# MySXMotion-V1_2-001.net
KiCad netlist of a schematic drawn in EAGLE
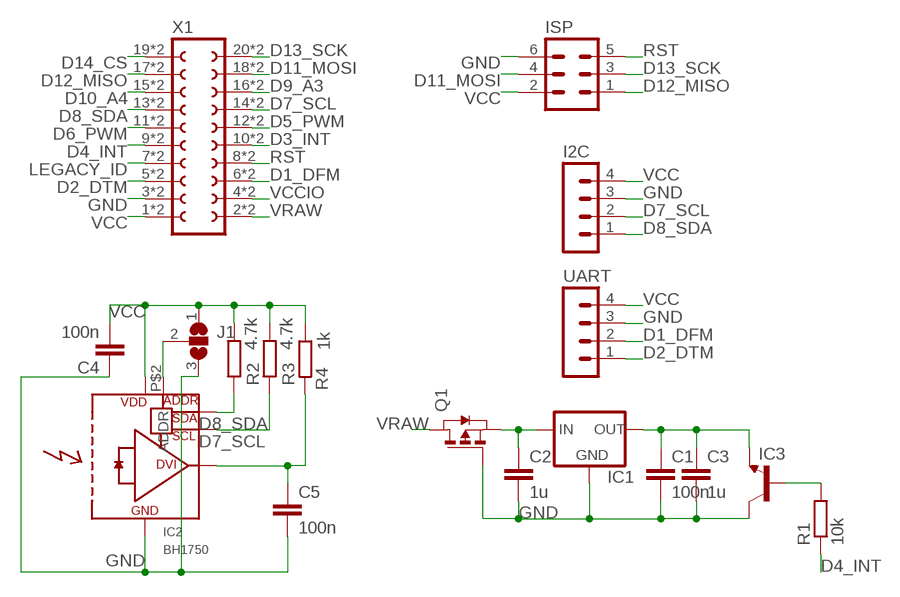
[diagram p0: schematic, sheet 1]

(export (version "E")
  (design (tool "Eeschema 10.0.6"))
  (components
    (comp (ref "C1")
      (value "100n")
      (footprint "eagle-import:C0603")
      (libsource (lib "eagle-import") (part "C-EUC0603"))
    )
    (comp (ref "C2")
      (value "1u")
      (footprint "eagle-import:C0603")
      (libsource (lib "eagle-import") (part "C-EUC0603"))
    )
    (comp (ref "C3")
      (value "1u")
      (footprint "eagle-import:C0805")
      (libsource (lib "eagle-import") (part "C-EUC0805"))
    )
    (comp (ref "C4")
      (value "100n")
      (footprint "eagle-import:C0603")
      (libsource (lib "eagle-import") (part "C-EUC0603"))
    )
    (comp (ref "C5")
      (value "100n")
      (footprint "eagle-import:C0603")
      (libsource (lib "eagle-import") (part "C-EUC0603"))
    )
    (comp (ref "I2C")
      (value "MA04-1")
      (footprint "eagle-import:MA04-1")
      (libsource (lib "eagle-import") (part "MA04-1"))
    )
    (comp (ref "IC1")
      (value "XC63FPM")
      (footprint "eagle-import:SOT23")
      (libsource (lib "eagle-import") (part "XC63FPM"))
    )
    (comp (ref "IC2")
      (value "BH1750")
      (footprint "eagle-import:WSOF6")
      (libsource (lib "eagle-import") (part "BH1750"))
    )
    (comp (ref "IC3")
      (value "-NPN-TO5")
      (footprint "eagle-import:TO5")
      (libsource (lib "eagle-import") (part "-NPN-TO5"))
    )
    (comp (ref "ISP")
      (value "MA03-2")
      (footprint "eagle-import:MA03-2")
      (libsource (lib "eagle-import") (part "MA03-2"))
    )
    (comp (ref "J1")
      (value "SJ2W")
      (footprint "eagle-import:SJ_2")
      (libsource (lib "eagle-import") (part "SJ2W"))
    )
    (comp (ref "Q1")
      (value "PMOSSOT23")
      (footprint "eagle-import:SOT-23")
      (libsource (lib "eagle-import") (part "PMOSSOT23"))
    )
    (comp (ref "R1")
      (value "10k")
      (footprint "eagle-import:R0603")
      (libsource (lib "eagle-import") (part "R-EU_R0603"))
    )
    (comp (ref "R2")
      (value "4.7k")
      (footprint "eagle-import:R0603")
      (libsource (lib "eagle-import") (part "R-EU_R0603"))
    )
    (comp (ref "R3")
      (value "4.7k")
      (footprint "eagle-import:R0603")
      (libsource (lib "eagle-import") (part "R-EU_R0603"))
    )
    (comp (ref "R4")
      (value "1k")
      (footprint "eagle-import:R0603")
      (libsource (lib "eagle-import") (part "R-EU_R0603"))
    )
    (comp (ref "UART")
      (value "MA04-1")
      (footprint "eagle-import:MA04-1")
      (libsource (lib "eagle-import") (part "MA04-1"))
    )
    (comp (ref "X1")
      (value "FE10-2")
      (footprint "eagle-import:FE10-2")
      (libsource (lib "eagle-import") (part "FE10-2"))
    )
  )
  (nets
    (net (code "1") (name "/D1_DFM") (class "Default")
      (node (ref "UART") (pin "2") (pinfunction "2_2") (pintype "passive"))
      (node (ref "X1") (pin "6") (pinfunction "6_6") (pintype "passive"))
      (node (ref "X1") (pin "P$6") (pinfunction "6_P$6") (pintype "passive"))
    )
    (net (code "2") (name "/D2_DTM") (class "Default")
      (node (ref "UART") (pin "1") (pinfunction "1_1") (pintype "passive"))
      (node (ref "X1") (pin "5") (pinfunction "5_5") (pintype "passive"))
      (node (ref "X1") (pin "P$5") (pinfunction "5_P$5") (pintype "passive"))
    )
    (net (code "3") (name "/D3_INT") (class "Default")
      (node (ref "X1") (pin "10") (pinfunction "10_10") (pintype "passive"))
      (node (ref "X1") (pin "P$10") (pinfunction "10_P$10") (pintype "passive"))
    )
    (net (code "4") (name "/D4_INT") (class "Default")
      (node (ref "R1") (pin "1") (pinfunction "1_1") (pintype "passive"))
      (node (ref "X1") (pin "9") (pinfunction "9_9") (pintype "passive"))
      (node (ref "X1") (pin "P$9") (pinfunction "9_P$9") (pintype "passive"))
    )
    (net (code "5") (name "/D5_PWM") (class "Default")
      (node (ref "X1") (pin "12") (pinfunction "12_12") (pintype "passive"))
      (node (ref "X1") (pin "P$12") (pinfunction "12_P$12") (pintype "passive"))
    )
    (net (code "6") (name "/D6_PWM") (class "Default")
      (node (ref "X1") (pin "11") (pinfunction "11_11") (pintype "passive"))
      (node (ref "X1") (pin "P$11") (pinfunction "11_P$11") (pintype "passive"))
    )
    (net (code "7") (name "/D7_SCL") (class "Default")
      (node (ref "I2C") (pin "2") (pinfunction "2_2") (pintype "passive"))
      (node (ref "IC2") (pin "P$6") (pinfunction "SCL_P$6") (pintype "input"))
      (node (ref "R3") (pin "1") (pinfunction "1_1") (pintype "passive"))
      (node (ref "X1") (pin "14") (pinfunction "14_14") (pintype "passive"))
      (node (ref "X1") (pin "P$14") (pinfunction "14_P$14") (pintype "passive"))
    )
    (net (code "8") (name "/D8_SDA") (class "Default")
      (node (ref "I2C") (pin "1") (pinfunction "1_1") (pintype "passive"))
      (node (ref "IC2") (pin "P$4") (pinfunction "SDA_P$4") (pintype "bidirectional"))
      (node (ref "R2") (pin "1") (pinfunction "1_1") (pintype "passive"))
      (node (ref "X1") (pin "13") (pinfunction "13_13") (pintype "passive"))
      (node (ref "X1") (pin "P$13") (pinfunction "13_P$13") (pintype "passive"))
    )
    (net (code "9") (name "/D9_A3") (class "Default")
      (node (ref "X1") (pin "16") (pinfunction "16_16") (pintype "passive"))
      (node (ref "X1") (pin "P$16") (pinfunction "16_P$16") (pintype "passive"))
    )
    (net (code "10") (name "/D10_A4") (class "Default")
      (node (ref "X1") (pin "15") (pinfunction "15_15") (pintype "passive"))
      (node (ref "X1") (pin "P$15") (pinfunction "15_P$15") (pintype "passive"))
    )
    (net (code "11") (name "/D11_MOSI") (class "Default")
      (node (ref "ISP") (pin "4") (pinfunction "4_4") (pintype "passive"))
      (node (ref "X1") (pin "18") (pinfunction "18_18") (pintype "passive"))
      (node (ref "X1") (pin "P$18") (pinfunction "18_P$18") (pintype "passive"))
    )
    (net (code "12") (name "/D12_MISO") (class "Default")
      (node (ref "ISP") (pin "1") (pinfunction "1_1") (pintype "passive"))
      (node (ref "X1") (pin "17") (pinfunction "17_17") (pintype "passive"))
      (node (ref "X1") (pin "P$17") (pinfunction "17_P$17") (pintype "passive"))
    )
    (net (code "13") (name "/D13_SCK") (class "Default")
      (node (ref "ISP") (pin "3") (pinfunction "3_3") (pintype "passive"))
      (node (ref "X1") (pin "20") (pinfunction "20_20") (pintype "passive"))
      (node (ref "X1") (pin "P$20") (pinfunction "20_P$20") (pintype "passive"))
    )
    (net (code "14") (name "/D14_CS") (class "Default")
      (node (ref "X1") (pin "19") (pinfunction "19_19") (pintype "passive"))
      (node (ref "X1") (pin "P$19") (pinfunction "19_P$19") (pintype "passive"))
    )
    (net (code "15") (name "/GND") (class "Default")
      (node (ref "C1") (pin "2") (pinfunction "2_2") (pintype "passive"))
      (node (ref "C2") (pin "2") (pinfunction "2_2") (pintype "passive"))
      (node (ref "C3") (pin "2") (pinfunction "2_2") (pintype "passive"))
      (node (ref "C4") (pin "1") (pinfunction "1_1") (pintype "passive"))
      (node (ref "C5") (pin "2") (pinfunction "2_2") (pintype "passive"))
      (node (ref "I2C") (pin "3") (pinfunction "3_3") (pintype "passive"))
      (node (ref "IC1") (pin "1") (pinfunction "GND_1") (pintype "input"))
      (node (ref "IC2") (pin "P$3") (pinfunction "GND_P$3") (pintype "power_in"))
      (node (ref "IC3") (pin "3") (pinfunction "C_3") (pintype "passive"))
      (node (ref "ISP") (pin "6") (pinfunction "6_6") (pintype "passive"))
      (node (ref "J1") (pin "3") (pinfunction "3_3") (pintype "passive"))
      (node (ref "Q1") (pin "3") (pinfunction "G_3") (pintype "passive"))
      (node (ref "UART") (pin "3") (pinfunction "3_3") (pintype "passive"))
      (node (ref "X1") (pin "3") (pinfunction "3_3") (pintype "passive"))
      (node (ref "X1") (pin "P$3") (pinfunction "3_P$3") (pintype "passive"))
    )
    (net (code "16") (name "/LEGACY_ID") (class "Default")
      (node (ref "X1") (pin "7") (pinfunction "7_7") (pintype "passive"))
      (node (ref "X1") (pin "P$7") (pinfunction "7_P$7") (pintype "passive"))
    )
    (net (code "17") (name "/RST") (class "Default")
      (node (ref "ISP") (pin "5") (pinfunction "5_5") (pintype "passive"))
      (node (ref "X1") (pin "8") (pinfunction "8_8") (pintype "passive"))
      (node (ref "X1") (pin "P$8") (pinfunction "8_P$8") (pintype "passive"))
    )
    (net (code "18") (name "/VCC") (class "Default")
      (node (ref "C4") (pin "2") (pinfunction "2_2") (pintype "passive"))
      (node (ref "I2C") (pin "4") (pinfunction "4_4") (pintype "passive"))
      (node (ref "IC2") (pin "P$1") (pinfunction "VCC_P$1") (pintype "power_in"))
      (node (ref "ISP") (pin "2") (pinfunction "2_2") (pintype "passive"))
      (node (ref "J1") (pin "1") (pinfunction "1_1") (pintype "passive"))
      (node (ref "R2") (pin "2") (pinfunction "2_2") (pintype "passive"))
      (node (ref "R3") (pin "2") (pinfunction "2_2") (pintype "passive"))
      (node (ref "R4") (pin "1") (pinfunction "1_1") (pintype "passive"))
      (node (ref "UART") (pin "4") (pinfunction "4_4") (pintype "passive"))
      (node (ref "X1") (pin "1") (pinfunction "1_1") (pintype "passive"))
      (node (ref "X1") (pin "P$1") (pinfunction "1_P$1") (pintype "passive"))
    )
    (net (code "19") (name "/VCCIO") (class "Default")
      (node (ref "X1") (pin "4") (pinfunction "4_4") (pintype "passive"))
      (node (ref "X1") (pin "P$4") (pinfunction "4_P$4") (pintype "passive"))
    )
    (net (code "20") (name "/VRAW") (class "Default")
      (node (ref "Q1") (pin "1") (pinfunction "D_1") (pintype "passive"))
      (node (ref "X1") (pin "2") (pinfunction "2_2") (pintype "passive"))
      (node (ref "X1") (pin "P$2") (pinfunction "2_P$2") (pintype "passive"))
    )
    (net (code "21") (name "Net-(IC1-IN)") (class "Default")
      (node (ref "C2") (pin "1") (pinfunction "1_1") (pintype "passive"))
      (node (ref "IC1") (pin "3") (pinfunction "IN_3") (pintype "input"))
      (node (ref "Q1") (pin "2") (pinfunction "S_2") (pintype "passive"))
    )
    (net (code "22") (name "Net-(IC1-OUT)") (class "Default")
      (node (ref "C1") (pin "1") (pinfunction "1_1") (pintype "passive"))
      (node (ref "C3") (pin "1") (pinfunction "1_1") (pintype "passive"))
      (node (ref "IC1") (pin "2") (pinfunction "OUT_2") (pintype "passive"))
      (node (ref "IC3") (pin "1") (pinfunction "E_1") (pintype "passive"))
    )
    (net (code "23") (name "Net-(IC2-ADDR)") (class "Default")
      (node (ref "IC2") (pin "P$2") (pinfunction "ADDR_P$2") (pintype "input"))
      (node (ref "J1") (pin "2") (pinfunction "2_2") (pintype "passive"))
    )
    (net (code "24") (name "Net-(IC2-DVI)") (class "Default")
      (node (ref "C5") (pin "1") (pinfunction "1_1") (pintype "passive"))
      (node (ref "IC2") (pin "P$5") (pinfunction "DVI_P$5") (pintype "output"))
      (node (ref "R4") (pin "2") (pinfunction "2_2") (pintype "passive"))
    )
    (net (code "25") (name "Net-(IC3-B)") (class "Default")
      (node (ref "IC3") (pin "2") (pinfunction "B_2") (pintype "passive"))
      (node (ref "R1") (pin "2") (pinfunction "2_2") (pintype "passive"))
    )
  )
)
